# 7880_IO.net
KiCad netlist of a schematic drawn in EAGLE
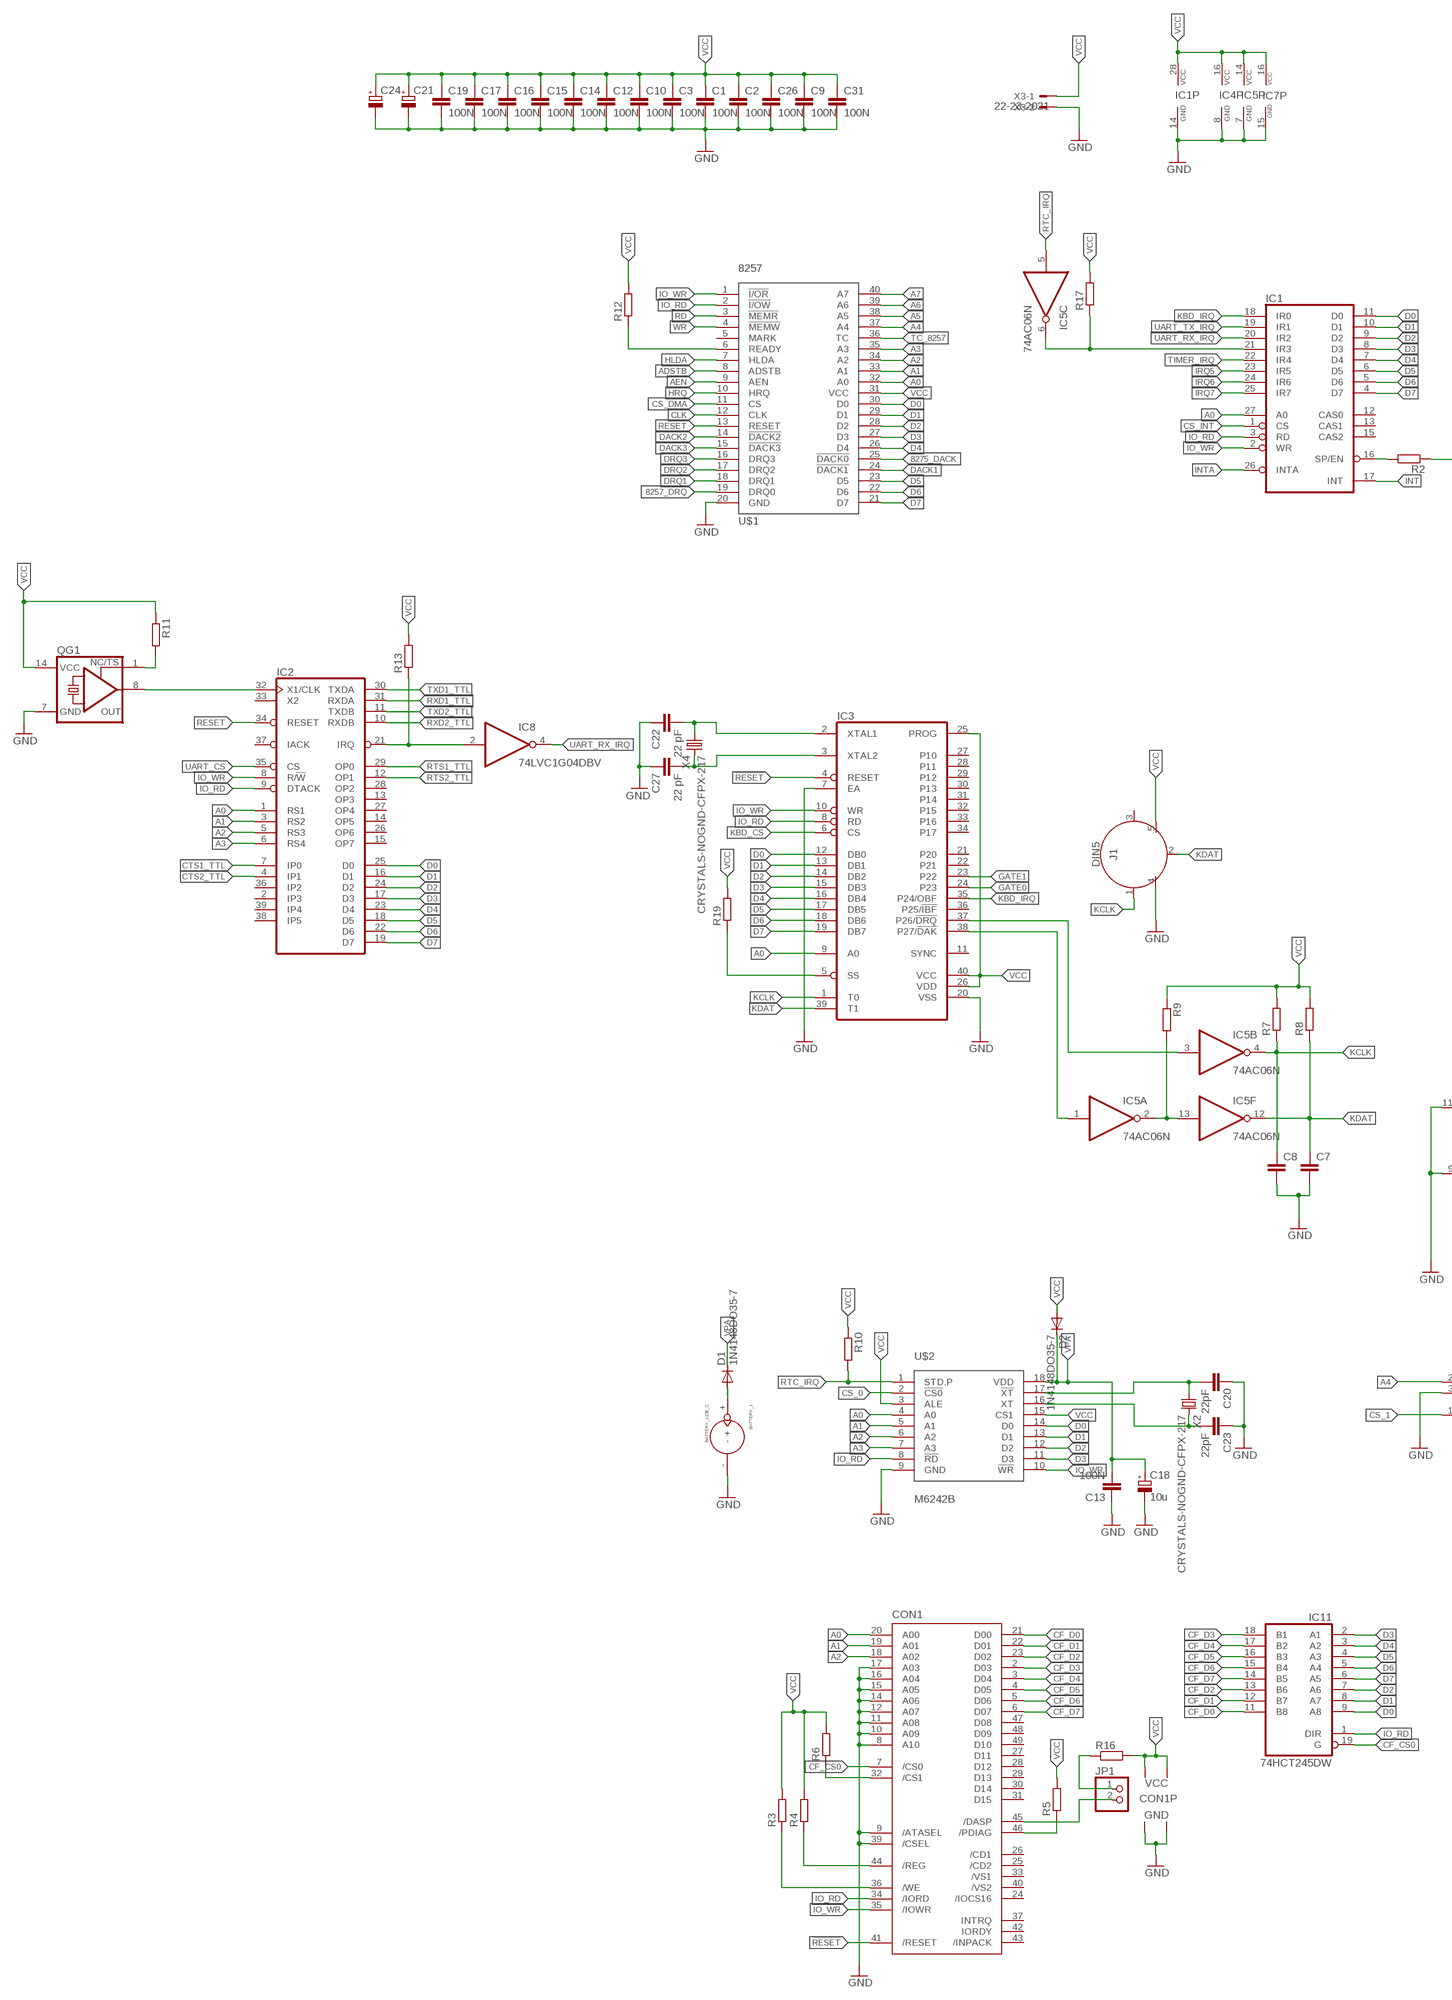
[diagram p0: schematic, sheet 1, part 1 of 2]
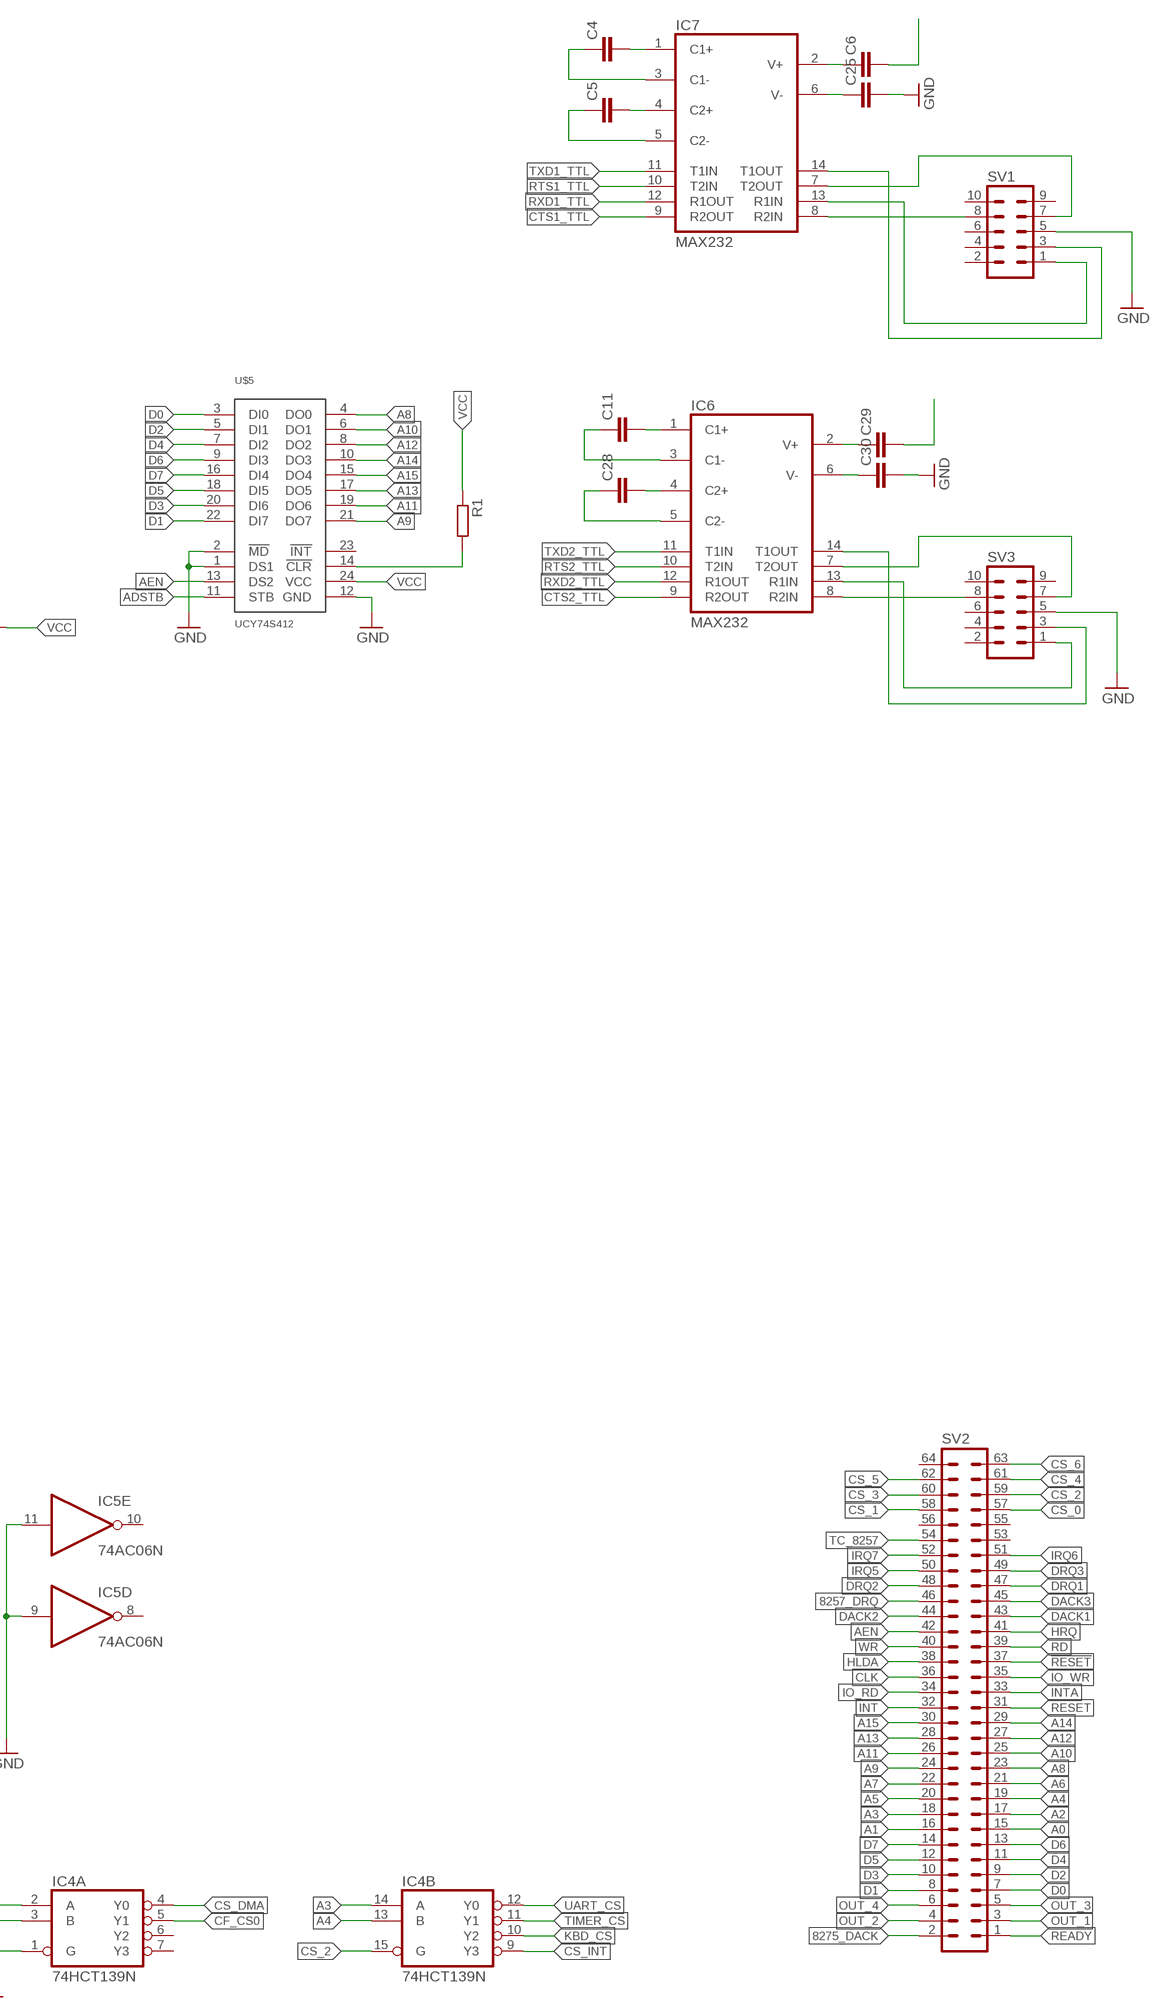
[diagram p1: schematic, sheet 1, part 2 of 2]

(export (version "E")
  (design (tool "Eeschema 10.0.6"))
  (components
    (comp (ref "BATTERY_1")
      (value "BATTERY_1236_C")
      (footprint "eagle-import:BATTERY_1236_C")
      (libsource (lib "eagle-import") (part "BATTERY_1236_C"))
    )
    (comp (ref "C1")
      (value "100N")
      (footprint "eagle-import:C0603")
      (libsource (lib "eagle-import") (part "C-EUC0603"))
    )
    (comp (ref "C2")
      (value "100N")
      (footprint "eagle-import:C0603")
      (libsource (lib "eagle-import") (part "C-EUC0603"))
    )
    (comp (ref "C3")
      (value "100N")
      (footprint "eagle-import:C0603")
      (libsource (lib "eagle-import") (part "C-EUC0603"))
    )
    (comp (ref "C4")
      (value "C-EUC0603")
      (footprint "eagle-import:C0603")
      (libsource (lib "eagle-import") (part "C-EUC0603"))
    )
    (comp (ref "C5")
      (value "C-EUC0603")
      (footprint "eagle-import:C0603")
      (libsource (lib "eagle-import") (part "C-EUC0603"))
    )
    (comp (ref "C6")
      (value "C-EUC0603")
      (footprint "eagle-import:C0603")
      (libsource (lib "eagle-import") (part "C-EUC0603"))
    )
    (comp (ref "C7")
      (value "C-EUC0603")
      (footprint "eagle-import:C0603")
      (libsource (lib "eagle-import") (part "C-EUC0603"))
    )
    (comp (ref "C8")
      (value "C-EUC0603")
      (footprint "eagle-import:C0603")
      (libsource (lib "eagle-import") (part "C-EUC0603"))
    )
    (comp (ref "C9")
      (value "100N")
      (footprint "eagle-import:C0603")
      (libsource (lib "eagle-import") (part "C-EUC0603"))
    )
    (comp (ref "C10")
      (value "100N")
      (footprint "eagle-import:C0603")
      (libsource (lib "eagle-import") (part "C-EUC0603"))
    )
    (comp (ref "C11")
      (value "C-EUC0603")
      (footprint "eagle-import:C0603")
      (libsource (lib "eagle-import") (part "C-EUC0603"))
    )
    (comp (ref "C12")
      (value "100N")
      (footprint "eagle-import:C0603")
      (libsource (lib "eagle-import") (part "C-EUC0603"))
    )
    (comp (ref "C13")
      (value "100N")
      (footprint "eagle-import:C0603")
      (libsource (lib "eagle-import") (part "C-EUC0603"))
    )
    (comp (ref "C14")
      (value "100N")
      (footprint "eagle-import:C0603")
      (libsource (lib "eagle-import") (part "C-EUC0603"))
    )
    (comp (ref "C15")
      (value "100N")
      (footprint "eagle-import:C0603")
      (libsource (lib "eagle-import") (part "C-EUC0603"))
    )
    (comp (ref "C16")
      (value "100N")
      (footprint "eagle-import:C0603")
      (libsource (lib "eagle-import") (part "C-EUC0603"))
    )
    (comp (ref "C17")
      (value "100N")
      (footprint "eagle-import:C0603")
      (libsource (lib "eagle-import") (part "C-EUC0603"))
    )
    (comp (ref "C18")
      (value "10u")
      (footprint "eagle-import:SMC_B")
      (libsource (lib "eagle-import") (part "CPOL-EUSMCB"))
    )
    (comp (ref "C19")
      (value "100N")
      (footprint "eagle-import:C0603")
      (libsource (lib "eagle-import") (part "C-EUC0603"))
    )
    (comp (ref "C20")
      (value "22pF")
      (footprint "eagle-import:C0603")
      (libsource (lib "eagle-import") (part "C-EUC0603"))
    )
    (comp (ref "C21")
      (value "CPOL-EUE3.5-8")
      (footprint "eagle-import:E3,5-8")
      (libsource (lib "eagle-import") (part "CPOL-EUE3.5-8"))
    )
    (comp (ref "C22")
      (value "22 pF")
      (footprint "eagle-import:C0603")
      (libsource (lib "eagle-import") (part "C-EUC0603"))
    )
    (comp (ref "C23")
      (value "22pF")
      (footprint "eagle-import:C0603")
      (libsource (lib "eagle-import") (part "C-EUC0603"))
    )
    (comp (ref "C24")
      (value "CPOL-EUSMCB")
      (footprint "eagle-import:SMC_B")
      (libsource (lib "eagle-import") (part "CPOL-EUSMCB"))
    )
    (comp (ref "C25")
      (value "C-EUC0603")
      (footprint "eagle-import:C0603")
      (libsource (lib "eagle-import") (part "C-EUC0603"))
    )
    (comp (ref "C26")
      (value "100N")
      (footprint "eagle-import:C0603")
      (libsource (lib "eagle-import") (part "C-EUC0603"))
    )
    (comp (ref "C27")
      (value "22 pF")
      (footprint "eagle-import:C0603")
      (libsource (lib "eagle-import") (part "C-EUC0603"))
    )
    (comp (ref "C28")
      (value "C-EUC0603")
      (footprint "eagle-import:C0603")
      (libsource (lib "eagle-import") (part "C-EUC0603"))
    )
    (comp (ref "C29")
      (value "C-EUC0603")
      (footprint "eagle-import:C0603")
      (libsource (lib "eagle-import") (part "C-EUC0603"))
    )
    (comp (ref "C30")
      (value "C-EUC0603")
      (footprint "eagle-import:C0603")
      (libsource (lib "eagle-import") (part "C-EUC0603"))
    )
    (comp (ref "C31")
      (value "100N")
      (footprint "eagle-import:C0603")
      (libsource (lib "eagle-import") (part "C-EUC0603"))
    )
    (comp (ref "CON1")
      (value "CF-CARD-IDE_MODE")
      (footprint "eagle-import:MI20-50PD-SF")
      (libsource (lib "eagle-import") (part "CF-CARD-IDE_MODE"))
    )
    (comp (ref "D1")
      (value "1N4148DO35-7")
      (footprint "eagle-import:DO35-7")
      (libsource (lib "eagle-import") (part "1N4148DO35-7"))
    )
    (comp (ref "D2")
      (value "1N4148DO35-7")
      (footprint "eagle-import:DO35-7")
      (libsource (lib "eagle-import") (part "1N4148DO35-7"))
    )
    (comp (ref "IC1")
      (value "8259A")
      (footprint "eagle-import:DIL28-6")
      (libsource (lib "eagle-import") (part "8259A"))
    )
    (comp (ref "IC2")
      (value "MC68681P")
      (footprint "eagle-import:DIL40")
      (libsource (lib "eagle-import") (part "MC68681P"))
    )
    (comp (ref "IC3")
      (value "UPI-8042AH")
      (footprint "eagle-import:DIL40")
      (libsource (lib "eagle-import") (part "UPI-8042AH"))
    )
    (comp (ref "IC4")
      (value "74HCT139N")
      (footprint "eagle-import:DIL16")
      (libsource (lib "eagle-import") (part "74139NHCT"))
    )
    (comp (ref "IC5")
      (value "74AC06N")
      (footprint "eagle-import:DIL14")
      (libsource (lib "eagle-import") (part "7406NAC"))
    )
    (comp (ref "IC6")
      (value "MAX232")
      (footprint "eagle-import:DIL16")
      (fields (field (name "MF") "MAXIM") (field (name "MPN") "MAX232ACPE+"))
      (libsource (lib "eagle-import") (part "MAX232"))
    )
    (comp (ref "IC7")
      (value "MAX232")
      (footprint "eagle-import:DIL16")
      (fields (field (name "MF") "MAXIM") (field (name "MPN") "MAX232ACPE+"))
      (libsource (lib "eagle-import") (part "MAX232"))
    )
    (comp (ref "IC8")
      (value "74LVC1G04DBV")
      (footprint "eagle-import:SOT23-5")
      (libsource (lib "eagle-import") (part "741G04DBVLVC"))
    )
    (comp (ref "IC11")
      (value "74HCT245DW")
      (footprint "eagle-import:SO20W")
      (libsource (lib "eagle-import") (part "74245DWHCT"))
    )
    (comp (ref "J1")
      (value "DIN5")
      (footprint "eagle-import:DIN5-RA-PTH")
      (libsource (lib "eagle-import") (part "DIN5"))
    )
    (comp (ref "JP1")
      (value "PINHD-1X2")
      (footprint "eagle-import:1X02")
      (libsource (lib "eagle-import") (part "PINHD-1X2"))
    )
    (comp (ref "QG1")
      (value "XO-14")
      (footprint "eagle-import:DIL14S")
      (libsource (lib "eagle-import") (part "XO-14"))
    )
    (comp (ref "R1")
      (value "R-EU_R0603")
      (footprint "eagle-import:R0603")
      (libsource (lib "eagle-import") (part "R-EU_R0603"))
    )
    (comp (ref "R2")
      (value "R-EU_R0603")
      (footprint "eagle-import:R0603")
      (libsource (lib "eagle-import") (part "R-EU_R0603"))
    )
    (comp (ref "R3")
      (value "R-EU_R0603")
      (footprint "eagle-import:R0603")
      (libsource (lib "eagle-import") (part "R-EU_R0603"))
    )
    (comp (ref "R4")
      (value "R-EU_0204/7")
      (footprint "eagle-import:0204_7")
      (libsource (lib "eagle-import") (part "R-EU_0204/7"))
    )
    (comp (ref "R5")
      (value "R-EU_0207/10")
      (footprint "eagle-import:0207_10")
      (libsource (lib "eagle-import") (part "R-EU_0207/10"))
    )
    (comp (ref "R6")
      (value "R-EU_R0603")
      (footprint "eagle-import:R0603")
      (libsource (lib "eagle-import") (part "R-EU_R0603"))
    )
    (comp (ref "R7")
      (value "R-EU_0204/5")
      (footprint "eagle-import:0204_5")
      (libsource (lib "eagle-import") (part "R-EU_0204/5"))
    )
    (comp (ref "R8")
      (value "R-EU_M0805")
      (footprint "eagle-import:M0805")
      (libsource (lib "eagle-import") (part "R-EU_M0805"))
    )
    (comp (ref "R9")
      (value "R-EU_R0603")
      (footprint "eagle-import:R0603")
      (libsource (lib "eagle-import") (part "R-EU_R0603"))
    )
    (comp (ref "R10")
      (value "R-EU_R0603")
      (footprint "eagle-import:R0603")
      (libsource (lib "eagle-import") (part "R-EU_R0603"))
    )
    (comp (ref "R11")
      (value "R-EU_R0603")
      (footprint "eagle-import:R0603")
      (libsource (lib "eagle-import") (part "R-EU_R0603"))
    )
    (comp (ref "R12")
      (value "R-EU_R0603")
      (footprint "eagle-import:R0603")
      (libsource (lib "eagle-import") (part "R-EU_R0603"))
    )
    (comp (ref "R13")
      (value "R-EU_0204/7")
      (footprint "eagle-import:0204_7")
      (libsource (lib "eagle-import") (part "R-EU_0204/7"))
    )
    (comp (ref "R16")
      (value "R-EU_R0603")
      (footprint "eagle-import:R0603")
      (libsource (lib "eagle-import") (part "R-EU_R0603"))
    )
    (comp (ref "R17")
      (value "R-EU_0204/7")
      (footprint "eagle-import:0204_7")
      (libsource (lib "eagle-import") (part "R-EU_0204/7"))
    )
    (comp (ref "R19")
      (value "R-EU_0204/5")
      (footprint "eagle-import:0204_5")
      (libsource (lib "eagle-import") (part "R-EU_0204/5"))
    )
    (comp (ref "SV1")
      (value "ML10")
      (footprint "eagle-import:ML10")
      (libsource (lib "eagle-import") (part "ML10"))
    )
    (comp (ref "SV2")
      (value "ML64L")
      (footprint "eagle-import:ML64L")
      (libsource (lib "eagle-import") (part "ML64L"))
    )
    (comp (ref "SV3")
      (value "ML10")
      (footprint "eagle-import:ML10")
      (libsource (lib "eagle-import") (part "ML10"))
    )
    (comp (ref "U$1")
      (value "8257")
      (footprint "eagle-import:DIL40")
      (libsource (lib "eagle-import") (part "8257"))
    )
    (comp (ref "U$2")
      (value "M6242B")
      (footprint "eagle-import:DIL18")
      (libsource (lib "eagle-import") (part "M6242B"))
    )
    (comp (ref "U$5")
      (value "UCY74S412")
      (footprint "eagle-import:DIL24-6")
      (libsource (lib "eagle-import") (part "UCY74S412"))
    )
    (comp (ref "X2")
      (value "CRYSTALS-NOGND-CFPX-217")
      (footprint "eagle-import:3.2X1.5-2-PAD")
      (libsource (lib "eagle-import") (part "CRYSTALS-NOGND-CFPX-217"))
    )
    (comp (ref "X3")
      (value "22-23-2021")
      (footprint "eagle-import:22-23-2021")
      (fields (field (name "MF") "MOLEX"))
      (libsource (lib "eagle-import") (part "22-23-2021"))
    )
    (comp (ref "X4")
      (value "CRYSTALS-NOGND-CFPX-217")
      (footprint "eagle-import:3.2X1.5-2-PAD")
      (libsource (lib "eagle-import") (part "CRYSTALS-NOGND-CFPX-217"))
    )
  )
  (nets
    (net (code "1") (name "/~{RESET}") (class "Default")
      (node (ref "CON1") (pin "41") (pinfunction "/RESET_41") (pintype "input"))
      (node (ref "IC3") (pin "4") (pinfunction "RESET_4") (pintype "input"))
      (node (ref "SV2") (pin "37") (pinfunction "37_37") (pintype "passive"))
    )
    (net (code "2") (name "8257_DRQ") (class "Default")
      (node (ref "SV2") (pin "46") (pinfunction "46_46") (pintype "passive"))
      (node (ref "U$1") (pin "19") (pinfunction "DRQ0_19") (pintype "bidirectional"))
    )
    (net (code "3") (name "8275_DACK") (class "Default")
      (node (ref "SV2") (pin "2") (pinfunction "2_2") (pintype "passive"))
      (node (ref "U$1") (pin "25") (pinfunction "~{DACK0}_25") (pintype "bidirectional"))
    )
    (net (code "4") (name "A0") (class "Default")
      (node (ref "CON1") (pin "20") (pinfunction "A00_20") (pintype "input"))
      (node (ref "IC1") (pin "27") (pinfunction "A0_27") (pintype "input"))
      (node (ref "IC2") (pin "1") (pinfunction "RS1_1") (pintype "input"))
      (node (ref "IC3") (pin "9") (pinfunction "A0_9") (pintype "input"))
      (node (ref "SV2") (pin "15") (pinfunction "15_15") (pintype "passive"))
      (node (ref "U$1") (pin "32") (pinfunction "A0_32") (pintype "bidirectional"))
      (node (ref "U$2") (pin "4") (pinfunction "A0_4") (pintype "bidirectional"))
    )
    (net (code "5") (name "A1") (class "Default")
      (node (ref "CON1") (pin "19") (pinfunction "A01_19") (pintype "input"))
      (node (ref "IC2") (pin "3") (pinfunction "RS2_3") (pintype "input"))
      (node (ref "SV2") (pin "16") (pinfunction "16_16") (pintype "passive"))
      (node (ref "U$1") (pin "33") (pinfunction "A1_33") (pintype "bidirectional"))
      (node (ref "U$2") (pin "5") (pinfunction "A1_5") (pintype "bidirectional"))
    )
    (net (code "6") (name "A2") (class "Default")
      (node (ref "CON1") (pin "18") (pinfunction "A02_18") (pintype "input"))
      (node (ref "IC2") (pin "5") (pinfunction "RS3_5") (pintype "input"))
      (node (ref "SV2") (pin "17") (pinfunction "17_17") (pintype "passive"))
      (node (ref "U$1") (pin "34") (pinfunction "A2_34") (pintype "bidirectional"))
      (node (ref "U$2") (pin "6") (pinfunction "A2_6") (pintype "bidirectional"))
    )
    (net (code "7") (name "A3") (class "Default")
      (node (ref "IC2") (pin "6") (pinfunction "RS4_6") (pintype "input"))
      (node (ref "IC4") (pin "14") (pinfunction "A_14") (pintype "input"))
      (node (ref "SV2") (pin "18") (pinfunction "18_18") (pintype "passive"))
      (node (ref "U$1") (pin "35") (pinfunction "A3_35") (pintype "bidirectional"))
      (node (ref "U$2") (pin "7") (pinfunction "A3_7") (pintype "bidirectional"))
    )
    (net (code "8") (name "A4") (class "Default")
      (node (ref "IC4") (pin "13") (pinfunction "B_13") (pintype "input"))
      (node (ref "IC4") (pin "2") (pinfunction "A_2") (pintype "input"))
      (node (ref "SV2") (pin "19") (pinfunction "19_19") (pintype "passive"))
      (node (ref "U$1") (pin "37") (pinfunction "A4_37") (pintype "bidirectional"))
    )
    (net (code "9") (name "A5") (class "Default")
      (node (ref "SV2") (pin "20") (pinfunction "20_20") (pintype "passive"))
      (node (ref "U$1") (pin "38") (pinfunction "A5_38") (pintype "bidirectional"))
    )
    (net (code "10") (name "A6") (class "Default")
      (node (ref "SV2") (pin "21") (pinfunction "21_21") (pintype "passive"))
      (node (ref "U$1") (pin "39") (pinfunction "A6_39") (pintype "bidirectional"))
    )
    (net (code "11") (name "A7") (class "Default")
      (node (ref "SV2") (pin "22") (pinfunction "22_22") (pintype "passive"))
      (node (ref "U$1") (pin "40") (pinfunction "A7_40") (pintype "bidirectional"))
    )
    (net (code "12") (name "A8") (class "Default")
      (node (ref "SV2") (pin "23") (pinfunction "23_23") (pintype "passive"))
      (node (ref "U$5") (pin "4") (pinfunction "DO0_4") (pintype "bidirectional"))
    )
    (net (code "13") (name "A9") (class "Default")
      (node (ref "SV2") (pin "24") (pinfunction "24_24") (pintype "passive"))
      (node (ref "U$5") (pin "21") (pinfunction "DO7_21") (pintype "bidirectional"))
    )
    (net (code "14") (name "A10") (class "Default")
      (node (ref "SV2") (pin "25") (pinfunction "25_25") (pintype "passive"))
      (node (ref "U$5") (pin "6") (pinfunction "DO1_6") (pintype "bidirectional"))
    )
    (net (code "15") (name "A11") (class "Default")
      (node (ref "SV2") (pin "26") (pinfunction "26_26") (pintype "passive"))
      (node (ref "U$5") (pin "19") (pinfunction "DO6_19") (pintype "bidirectional"))
    )
    (net (code "16") (name "A12") (class "Default")
      (node (ref "SV2") (pin "27") (pinfunction "27_27") (pintype "passive"))
      (node (ref "U$5") (pin "8") (pinfunction "DO2_8") (pintype "bidirectional"))
    )
    (net (code "17") (name "A13") (class "Default")
      (node (ref "SV2") (pin "28") (pinfunction "28_28") (pintype "passive"))
      (node (ref "U$5") (pin "17") (pinfunction "DO5_17") (pintype "bidirectional"))
    )
    (net (code "18") (name "A14") (class "Default")
      (node (ref "SV2") (pin "29") (pinfunction "29_29") (pintype "passive"))
      (node (ref "U$5") (pin "10") (pinfunction "DO3_10") (pintype "bidirectional"))
    )
    (net (code "19") (name "A15") (class "Default")
      (node (ref "SV2") (pin "30") (pinfunction "30_30") (pintype "passive"))
      (node (ref "U$5") (pin "15") (pinfunction "DO4_15") (pintype "bidirectional"))
    )
    (net (code "20") (name "ADSTB") (class "Default")
      (node (ref "U$1") (pin "8") (pinfunction "ADSTB_8") (pintype "bidirectional"))
      (node (ref "U$5") (pin "11") (pinfunction "STB_11") (pintype "bidirectional"))
    )
    (net (code "21") (name "AEN") (class "Default")
      (node (ref "SV2") (pin "42") (pinfunction "42_42") (pintype "passive"))
      (node (ref "U$1") (pin "9") (pinfunction "AEN_9") (pintype "bidirectional"))
      (node (ref "U$5") (pin "13") (pinfunction "DS2_13") (pintype "bidirectional"))
    )
    (net (code "22") (name "CF_CS0") (class "Default")
      (node (ref "CON1") (pin "7") (pinfunction "/CS0_7") (pintype "input"))
      (node (ref "IC11") (pin "19") (pinfunction "G_19") (pintype "input"))
      (node (ref "IC4") (pin "5") (pinfunction "Y1_5") (pintype "output"))
    )
    (net (code "23") (name "CF_D0") (class "Default")
      (node (ref "CON1") (pin "21") (pinfunction "D00_21") (pintype "bidirectional"))
      (node (ref "IC11") (pin "11") (pinfunction "B8_11") (pintype "bidirectional"))
    )
    (net (code "24") (name "CF_D1") (class "Default")
      (node (ref "CON1") (pin "22") (pinfunction "D01_22") (pintype "bidirectional"))
      (node (ref "IC11") (pin "12") (pinfunction "B7_12") (pintype "bidirectional"))
    )
    (net (code "25") (name "CF_D2") (class "Default")
      (node (ref "CON1") (pin "23") (pinfunction "D02_23") (pintype "bidirectional"))
      (node (ref "IC11") (pin "13") (pinfunction "B6_13") (pintype "bidirectional"))
    )
    (net (code "26") (name "CF_D3") (class "Default")
      (node (ref "CON1") (pin "2") (pinfunction "D03_2") (pintype "bidirectional"))
      (node (ref "IC11") (pin "18") (pinfunction "B1_18") (pintype "bidirectional"))
    )
    (net (code "27") (name "CF_D4") (class "Default")
      (node (ref "CON1") (pin "3") (pinfunction "D04_3") (pintype "bidirectional"))
      (node (ref "IC11") (pin "17") (pinfunction "B2_17") (pintype "bidirectional"))
    )
    (net (code "28") (name "CF_D5") (class "Default")
      (node (ref "CON1") (pin "4") (pinfunction "D05_4") (pintype "bidirectional"))
      (node (ref "IC11") (pin "16") (pinfunction "B3_16") (pintype "bidirectional"))
    )
    (net (code "29") (name "CF_D6") (class "Default")
      (node (ref "CON1") (pin "5") (pinfunction "D06_5") (pintype "bidirectional"))
      (node (ref "IC11") (pin "15") (pinfunction "B4_15") (pintype "bidirectional"))
    )
    (net (code "30") (name "CF_D7") (class "Default")
      (node (ref "CON1") (pin "6") (pinfunction "D07_6") (pintype "bidirectional"))
      (node (ref "IC11") (pin "14") (pinfunction "B5_14") (pintype "bidirectional"))
    )
    (net (code "31") (name "CLK") (class "Default")
      (node (ref "SV2") (pin "36") (pinfunction "36_36") (pintype "passive"))
      (node (ref "U$1") (pin "12") (pinfunction "CLK_12") (pintype "bidirectional"))
    )
    (net (code "32") (name "CS_0") (class "Default")
      (node (ref "SV2") (pin "57") (pinfunction "57_57") (pintype "passive"))
      (node (ref "U$2") (pin "2") (pinfunction "~{CS0}_2") (pintype "bidirectional"))
    )
    (net (code "33") (name "CS_1") (class "Default")
      (node (ref "IC4") (pin "1") (pinfunction "G_1") (pintype "input"))
      (node (ref "SV2") (pin "58") (pinfunction "58_58") (pintype "passive"))
    )
    (net (code "34") (name "CS_2") (class "Default")
      (node (ref "IC4") (pin "15") (pinfunction "G_15") (pintype "input"))
      (node (ref "SV2") (pin "59") (pinfunction "59_59") (pintype "passive"))
    )
    (net (code "35") (name "CS_3") (class "Default")
      (node (ref "SV2") (pin "60") (pinfunction "60_60") (pintype "passive"))
    )
    (net (code "36") (name "CS_4") (class "Default")
      (node (ref "SV2") (pin "61") (pinfunction "61_61") (pintype "passive"))
    )
    (net (code "37") (name "CS_5") (class "Default")
      (node (ref "SV2") (pin "62") (pinfunction "62_62") (pintype "passive"))
    )
    (net (code "38") (name "CS_6") (class "Default")
      (node (ref "SV2") (pin "63") (pinfunction "63_63") (pintype "passive"))
    )
    (net (code "39") (name "CS_DMA") (class "Default")
      (node (ref "IC4") (pin "4") (pinfunction "Y0_4") (pintype "output"))
      (node (ref "U$1") (pin "11") (pinfunction "CS_11") (pintype "bidirectional"))
    )
    (net (code "40") (name "CS_INT") (class "Default")
      (node (ref "IC1") (pin "1") (pinfunction "CS_1") (pintype "input"))
      (node (ref "IC4") (pin "9") (pinfunction "Y3_9") (pintype "output"))
    )
    (net (code "41") (name "CTS1_TTL") (class "Default")
      (node (ref "IC2") (pin "7") (pinfunction "IP0_7") (pintype "input"))
      (node (ref "IC7") (pin "9") (pinfunction "R2OUT_9") (pintype "output"))
    )
    (net (code "42") (name "CTS2_TTL") (class "Default")
      (node (ref "IC2") (pin "4") (pinfunction "IP1_4") (pintype "input"))
      (node (ref "IC6") (pin "9") (pinfunction "R2OUT_9") (pintype "output"))
    )
    (net (code "43") (name "D0") (class "Default")
      (node (ref "IC1") (pin "11") (pinfunction "D0_11") (pintype "bidirectional"))
      (node (ref "IC11") (pin "9") (pinfunction "A8_9") (pintype "bidirectional"))
      (node (ref "IC2") (pin "25") (pinfunction "D0_25") (pintype "bidirectional"))
      (node (ref "IC3") (pin "12") (pinfunction "DB0_12") (pintype "bidirectional"))
      (node (ref "SV2") (pin "7") (pinfunction "7_7") (pintype "passive"))
      (node (ref "U$1") (pin "30") (pinfunction "D0_30") (pintype "bidirectional"))
      (node (ref "U$2") (pin "14") (pinfunction "D0_14") (pintype "bidirectional"))
      (node (ref "U$5") (pin "3") (pinfunction "DI0_3") (pintype "bidirectional"))
    )
    (net (code "44") (name "D1") (class "Default")
      (node (ref "IC1") (pin "10") (pinfunction "D1_10") (pintype "bidirectional"))
      (node (ref "IC11") (pin "8") (pinfunction "A7_8") (pintype "bidirectional"))
      (node (ref "IC2") (pin "16") (pinfunction "D1_16") (pintype "bidirectional"))
      (node (ref "IC3") (pin "13") (pinfunction "DB1_13") (pintype "bidirectional"))
      (node (ref "SV2") (pin "8") (pinfunction "8_8") (pintype "passive"))
      (node (ref "U$1") (pin "29") (pinfunction "D1_29") (pintype "bidirectional"))
      (node (ref "U$2") (pin "13") (pinfunction "D1_13") (pintype "bidirectional"))
      (node (ref "U$5") (pin "22") (pinfunction "DI7_22") (pintype "bidirectional"))
    )
    (net (code "45") (name "D2") (class "Default")
      (node (ref "IC1") (pin "9") (pinfunction "D2_9") (pintype "bidirectional"))
      (node (ref "IC11") (pin "7") (pinfunction "A6_7") (pintype "bidirectional"))
      (node (ref "IC2") (pin "24") (pinfunction "D2_24") (pintype "bidirectional"))
      (node (ref "IC3") (pin "14") (pinfunction "DB2_14") (pintype "bidirectional"))
      (node (ref "SV2") (pin "9") (pinfunction "9_9") (pintype "passive"))
      (node (ref "U$1") (pin "28") (pinfunction "D2_28") (pintype "bidirectional"))
      (node (ref "U$2") (pin "12") (pinfunction "D2_12") (pintype "bidirectional"))
      (node (ref "U$5") (pin "5") (pinfunction "DI1_5") (pintype "bidirectional"))
    )
    (net (code "46") (name "D3") (class "Default")
      (node (ref "IC1") (pin "8") (pinfunction "D3_8") (pintype "bidirectional"))
      (node (ref "IC11") (pin "2") (pinfunction "A1_2") (pintype "bidirectional"))
      (node (ref "IC2") (pin "17") (pinfunction "D3_17") (pintype "bidirectional"))
      (node (ref "IC3") (pin "15") (pinfunction "DB3_15") (pintype "bidirectional"))
      (node (ref "SV2") (pin "10") (pinfunction "10_10") (pintype "passive"))
      (node (ref "U$1") (pin "27") (pinfunction "D3_27") (pintype "bidirectional"))
      (node (ref "U$2") (pin "11") (pinfunction "D3_11") (pintype "bidirectional"))
      (node (ref "U$5") (pin "20") (pinfunction "DI6_20") (pintype "bidirectional"))
    )
    (net (code "47") (name "D4") (class "Default")
      (node (ref "IC1") (pin "7") (pinfunction "D4_7") (pintype "bidirectional"))
      (node (ref "IC11") (pin "3") (pinfunction "A2_3") (pintype "bidirectional"))
      (node (ref "IC2") (pin "23") (pinfunction "D4_23") (pintype "bidirectional"))
      (node (ref "IC3") (pin "16") (pinfunction "DB4_16") (pintype "bidirectional"))
      (node (ref "SV2") (pin "11") (pinfunction "11_11") (pintype "passive"))
      (node (ref "U$1") (pin "26") (pinfunction "D4_26") (pintype "bidirectional"))
      (node (ref "U$5") (pin "7") (pinfunction "DI2_7") (pintype "bidirectional"))
    )
    (net (code "48") (name "D5") (class "Default")
      (node (ref "IC1") (pin "6") (pinfunction "D5_6") (pintype "bidirectional"))
      (node (ref "IC11") (pin "4") (pinfunction "A3_4") (pintype "bidirectional"))
      (node (ref "IC2") (pin "18") (pinfunction "D5_18") (pintype "bidirectional"))
      (node (ref "IC3") (pin "17") (pinfunction "DB5_17") (pintype "bidirectional"))
      (node (ref "SV2") (pin "12") (pinfunction "12_12") (pintype "passive"))
      (node (ref "U$1") (pin "23") (pinfunction "D5_23") (pintype "bidirectional"))
      (node (ref "U$5") (pin "18") (pinfunction "DI5_18") (pintype "bidirectional"))
    )
    (net (code "49") (name "D6") (class "Default")
      (node (ref "IC1") (pin "5") (pinfunction "D6_5") (pintype "bidirectional"))
      (node (ref "IC11") (pin "5") (pinfunction "A4_5") (pintype "bidirectional"))
      (node (ref "IC2") (pin "22") (pinfunction "D6_22") (pintype "bidirectional"))
      (node (ref "IC3") (pin "18") (pinfunction "DB6_18") (pintype "bidirectional"))
      (node (ref "SV2") (pin "13") (pinfunction "13_13") (pintype "passive"))
      (node (ref "U$1") (pin "22") (pinfunction "D6_22") (pintype "bidirectional"))
      (node (ref "U$5") (pin "9") (pinfunction "DI3_9") (pintype "bidirectional"))
    )
    (net (code "50") (name "D7") (class "Default")
      (node (ref "IC1") (pin "4") (pinfunction "D7_4") (pintype "bidirectional"))
      (node (ref "IC11") (pin "6") (pinfunction "A5_6") (pintype "bidirectional"))
      (node (ref "IC2") (pin "19") (pinfunction "D7_19") (pintype "bidirectional"))
      (node (ref "IC3") (pin "19") (pinfunction "DB7_19") (pintype "bidirectional"))
      (node (ref "SV2") (pin "14") (pinfunction "14_14") (pintype "passive"))
      (node (ref "U$1") (pin "21") (pinfunction "D7_21") (pintype "bidirectional"))
      (node (ref "U$5") (pin "16") (pinfunction "DI4_16") (pintype "bidirectional"))
    )
    (net (code "51") (name "DACK1") (class "Default")
      (node (ref "SV2") (pin "43") (pinfunction "43_43") (pintype "passive"))
      (node (ref "U$1") (pin "24") (pinfunction "~{DACK1}_24") (pintype "bidirectional"))
    )
    (net (code "52") (name "DACK2") (class "Default")
      (node (ref "SV2") (pin "44") (pinfunction "44_44") (pintype "passive"))
      (node (ref "U$1") (pin "14") (pinfunction "~{DACK2}_14") (pintype "bidirectional"))
    )
    (net (code "53") (name "DACK3") (class "Default")
      (node (ref "SV2") (pin "45") (pinfunction "45_45") (pintype "passive"))
      (node (ref "U$1") (pin "15") (pinfunction "~{DACK3}_15") (pintype "bidirectional"))
    )
    (net (code "54") (name "DRQ1") (class "Default")
      (node (ref "SV2") (pin "47") (pinfunction "47_47") (pintype "passive"))
      (node (ref "U$1") (pin "18") (pinfunction "DRQ1_18") (pintype "bidirectional"))
    )
    (net (code "55") (name "DRQ2") (class "Default")
      (node (ref "SV2") (pin "48") (pinfunction "48_48") (pintype "passive"))
      (node (ref "U$1") (pin "17") (pinfunction "DRQ2_17") (pintype "bidirectional"))
    )
    (net (code "56") (name "DRQ3") (class "Default")
      (node (ref "SV2") (pin "49") (pinfunction "49_49") (pintype "passive"))
      (node (ref "U$1") (pin "16") (pinfunction "DRQ3_16") (pintype "bidirectional"))
    )
    (net (code "57") (name "GATE0") (class "Default")
      (node (ref "IC3") (pin "24") (pinfunction "P23_24") (pintype "bidirectional"))
    )
    (net (code "58") (name "GATE1") (class "Default")
      (node (ref "IC3") (pin "23") (pinfunction "P22_23") (pintype "bidirectional"))
    )
    (net (code "59") (name "GND") (class "Default")
      (node (ref "BATTERY_1") (pin "-") (pinfunction "-_-") (pintype "bidirectional"))
      (node (ref "C1") (pin "2") (pinfunction "2_2") (pintype "passive"))
      (node (ref "C10") (pin "2") (pinfunction "2_2") (pintype "passive"))
      (node (ref "C12") (pin "2") (pinfunction "2_2") (pintype "passive"))
      (node (ref "C13") (pin "1") (pinfunction "1_1") (pintype "passive"))
      (node (ref "C14") (pin "2") (pinfunction "2_2") (pintype "passive"))
      (node (ref "C15") (pin "2") (pinfunction "2_2") (pintype "passive"))
      (node (ref "C16") (pin "2") (pinfunction "2_2") (pintype "passive"))
      (node (ref "C17") (pin "2") (pinfunction "2_2") (pintype "passive"))
      (node (ref "C18") (pin "-") (pinfunction "-_-") (pintype "passive"))
      (node (ref "C19") (pin "2") (pinfunction "2_2") (pintype "passive"))
      (node (ref "C2") (pin "2") (pinfunction "2_2") (pintype "passive"))
      (node (ref "C20") (pin "1") (pinfunction "1_1") (pintype "passive"))
      (node (ref "C21") (pin "-") (pinfunction "-_-") (pintype "passive"))
      (node (ref "C22") (pin "1") (pinfunction "1_1") (pintype "passive"))
      (node (ref "C23") (pin "1") (pinfunction "1_1") (pintype "passive"))
      (node (ref "C24") (pin "-") (pinfunction "-_-") (pintype "passive"))
      (node (ref "C25") (pin "2") (pinfunction "2_2") (pintype "passive"))
      (node (ref "C26") (pin "2") (pinfunction "2_2") (pintype "passive"))
      (node (ref "C27") (pin "1") (pinfunction "1_1") (pintype "passive"))
      (node (ref "C3") (pin "2") (pinfunction "2_2") (pintype "passive"))
      (node (ref "C30") (pin "2") (pinfunction "2_2") (pintype "passive"))
      (node (ref "C31") (pin "2") (pinfunction "2_2") (pintype "passive"))
      (node (ref "C7") (pin "2") (pinfunction "2_2") (pintype "passive"))
      (node (ref "C8") (pin "2") (pinfunction "2_2") (pintype "passive"))
      (node (ref "C9") (pin "2") (pinfunction "2_2") (pintype "passive"))
      (node (ref "CON1") (pin "1") (pinfunction "GND1_1") (pintype "power_in"))
      (node (ref "CON1") (pin "10") (pinfunction "A09_10") (pintype "input"))
      (node (ref "CON1") (pin "11") (pinfunction "A08_11") (pintype "input"))
      (node (ref "CON1") (pin "12") (pinfunction "A07_12") (pintype "input"))
      (node (ref "CON1") (pin "14") (pinfunction "A06_14") (pintype "input"))
      (node (ref "CON1") (pin "15") (pinfunction "A05_15") (pintype "input"))
      (node (ref "CON1") (pin "16") (pinfunction "A04_16") (pintype "input"))
      (node (ref "CON1") (pin "17") (pinfunction "A03_17") (pintype "input"))
      (node (ref "CON1") (pin "39") (pinfunction "/CSEL_39") (pintype "input"))
      (node (ref "CON1") (pin "50") (pinfunction "GND2_50") (pintype "power_in"))
      (node (ref "CON1") (pin "8") (pinfunction "A10_8") (pintype "input"))
      (node (ref "CON1") (pin "9") (pinfunction "/ATASEL_9") (pintype "input"))
      (node (ref "IC1") (pin "14") (pinfunction "GND_14") (pintype "power_in"))
      (node (ref "IC3") (pin "20") (pinfunction "VSS_20") (pintype "power_in"))
      (node (ref "IC3") (pin "7") (pinfunction "EA_7") (pintype "input"))
      (node (ref "IC4") (pin "3") (pinfunction "B_3") (pintype "input"))
      (node (ref "IC4") (pin "8") (pinfunction "GND_8") (pintype "power_in"))
      (node (ref "IC5") (pin "11") (pinfunction "I_11") (pintype "input"))
      (node (ref "IC5") (pin "7") (pinfunction "GND_7") (pintype "power_in"))
      (node (ref "IC5") (pin "9") (pinfunction "I_9") (pintype "input"))
      (node (ref "IC7") (pin "15") (pinfunction "GND_15") (pintype "power_in"))
      (node (ref "J1") (pin "4") (pinfunction "4_4") (pintype "bidirectional"))
      (node (ref "QG1") (pin "7") (pinfunction "GND_7") (pintype "power_in"))
      (node (ref "SV1") (pin "5") (pinfunction "5_5") (pintype "passive"))
      (node (ref "SV3") (pin "5") (pinfunction "5_5") (pintype "passive"))
      (node (ref "U$1") (pin "20") (pinfunction "GND_20") (pintype "bidirectional"))
      (node (ref "U$2") (pin "9") (pinfunction "GND_9") (pintype "bidirectional"))
      (node (ref "U$5") (pin "1") (pinfunction "DS1_1") (pintype "bidirectional"))
      (node (ref "U$5") (pin "12") (pinfunction "GND_12") (pintype "bidirectional"))
      (node (ref "U$5") (pin "2") (pinfunction "~{MD}_2") (pintype "bidirectional"))
      (node (ref "X3") (pin "2") (pinfunction "S_2") (pintype "passive"))
    )
    (net (code "60") (name "HLDA") (class "Default")
      (node (ref "SV2") (pin "38") (pinfunction "38_38") (pintype "passive"))
      (node (ref "U$1") (pin "7") (pinfunction "HLDA_7") (pintype "bidirectional"))
    )
    (net (code "61") (name "HRQ") (class "Default")
      (node (ref "SV2") (pin "41") (pinfunction "41_41") (pintype "passive"))
      (node (ref "U$1") (pin "10") (pinfunction "HRQ_10") (pintype "bidirectional"))
    )
    (net (code "62") (name "INT") (class "Default")
      (node (ref "IC1") (pin "17") (pinfunction "INT_17") (pintype "output"))
      (node (ref "SV2") (pin "32") (pinfunction "32_32") (pintype "passive"))
    )
    (net (code "63") (name "INTA") (class "Default")
      (node (ref "IC1") (pin "26") (pinfunction "INTA_26") (pintype "input"))
      (node (ref "SV2") (pin "33") (pinfunction "33_33") (pintype "passive"))
    )
    (net (code "64") (name "IO_RD") (class "Default")
      (node (ref "CON1") (pin "34") (pinfunction "/IORD_34") (pintype "input"))
      (node (ref "IC1") (pin "3") (pinfunction "RD_3") (pintype "input"))
      (node (ref "IC11") (pin "1") (pinfunction "DIR_1") (pintype "input"))
      (node (ref "IC2") (pin "9") (pinfunction "DTACK_9") (pintype "output"))
      (node (ref "IC3") (pin "8") (pinfunction "RD_8") (pintype "input"))
      (node (ref "SV2") (pin "34") (pinfunction "34_34") (pintype "passive"))
      (node (ref "U$1") (pin "2") (pinfunction "~{I/OW}_2") (pintype "bidirectional"))
      (node (ref "U$2") (pin "8") (pinfunction "~{RD}_8") (pintype "bidirectional"))
    )
    (net (code "65") (name "IO_WR") (class "Default")
      (node (ref "CON1") (pin "35") (pinfunction "/IOWR_35") (pintype "input"))
      (node (ref "IC1") (pin "2") (pinfunction "WR_2") (pintype "input"))
      (node (ref "IC2") (pin "8") (pinfunction "R/~{W}_8") (pintype "input"))
      (node (ref "IC3") (pin "10") (pinfunction "WR_10") (pintype "input"))
      (node (ref "SV2") (pin "35") (pinfunction "35_35") (pintype "passive"))
      (node (ref "U$1") (pin "1") (pinfunction "~{I/OR}_1") (pintype "bidirectional"))
      (node (ref "U$2") (pin "10") (pinfunction "~{WR}_10") (pintype "bidirectional"))
    )
    (net (code "66") (name "IRQ5") (class "Default")
      (node (ref "IC1") (pin "23") (pinfunction "IR5_23") (pintype "input"))
      (node (ref "SV2") (pin "50") (pinfunction "50_50") (pintype "passive"))
    )
    (net (code "67") (name "IRQ6") (class "Default")
      (node (ref "IC1") (pin "24") (pinfunction "IR6_24") (pintype "input"))
      (node (ref "SV2") (pin "51") (pinfunction "51_51") (pintype "passive"))
    )
    (net (code "68") (name "IRQ7") (class "Default")
      (node (ref "IC1") (pin "25") (pinfunction "IR7_25") (pintype "input"))
      (node (ref "SV2") (pin "52") (pinfunction "52_52") (pintype "passive"))
    )
    (net (code "69") (name "KBD_CS") (class "Default")
      (node (ref "IC3") (pin "6") (pinfunction "CS_6") (pintype "input"))
      (node (ref "IC4") (pin "10") (pinfunction "Y2_10") (pintype "output"))
    )
    (net (code "70") (name "KBD_IRQ") (class "Default")
      (node (ref "IC1") (pin "18") (pinfunction "IR0_18") (pintype "input"))
      (node (ref "IC3") (pin "35") (pinfunction "P24/OBF_35") (pintype "bidirectional"))
    )
    (net (code "71") (name "KCLK") (class "Default")
      (node (ref "C8") (pin "1") (pinfunction "1_1") (pintype "passive"))
      (node (ref "IC3") (pin "1") (pinfunction "T0_1") (pintype "input"))
      (node (ref "IC5") (pin "4") (pinfunction "O_4") (pintype "open_collector"))
      (node (ref "J1") (pin "1") (pinfunction "1_1") (pintype "bidirectional"))
      (node (ref "R7") (pin "1") (pinfunction "1_1") (pintype "passive"))
    )
    (net (code "72") (name "KDAT") (class "Default")
      (node (ref "C7") (pin "1") (pinfunction "1_1") (pintype "passive"))
      (node (ref "IC3") (pin "39") (pinfunction "T1_39") (pintype "input"))
      (node (ref "IC5") (pin "12") (pinfunction "O_12") (pintype "open_collector"))
      (node (ref "J1") (pin "2") (pinfunction "2_2") (pintype "bidirectional"))
      (node (ref "R8") (pin "1") (pinfunction "1_1") (pintype "passive"))
    )
    (net (code "73") (name "Net-(BATTERY_1-Pad+)") (class "Default")
      (node (ref "BATTERY_1") (pin "+") (pinfunction "+_+") (pintype "bidirectional"))
      (node (ref "D1") (pin "A") (pinfunction "A_A") (pintype "passive"))
    )
    (net (code "74") (name "Net-(CON1A-{slash}CS1)") (class "Default")
      (node (ref "CON1") (pin "32") (pinfunction "/CS1_32") (pintype "input"))
      (node (ref "R6") (pin "1") (pinfunction "1_1") (pintype "passive"))
    )
    (net (code "75") (name "Net-(CON1A-{slash}DASP)") (class "Default")
      (node (ref "CON1") (pin "45") (pinfunction "/DASP_45") (pintype "bidirectional"))
      (node (ref "JP1") (pin "2") (pinfunction "2_2") (pintype "passive"))
    )
    (net (code "76") (name "Net-(CON1A-{slash}PDIAG)") (class "Default")
      (node (ref "CON1") (pin "46") (pinfunction "/PDIAG_46") (pintype "bidirectional"))
      (node (ref "R5") (pin "1") (pinfunction "1_1") (pintype "passive"))
    )
    (net (code "77") (name "Net-(CON1A-{slash}REG)") (class "Default")
      (node (ref "CON1") (pin "44") (pinfunction "/REG_44") (pintype "input"))
      (node (ref "R4") (pin "1") (pinfunction "1_1") (pintype "passive"))
    )
    (net (code "78") (name "Net-(CON1A-{slash}WE)") (class "Default")
      (node (ref "CON1") (pin "36") (pinfunction "/WE_36") (pintype "input"))
      (node (ref "R3") (pin "1") (pinfunction "1_1") (pintype "passive"))
    )
    (net (code "79") (name "Net-(IC1A-IR3)") (class "Default")
      (node (ref "IC1") (pin "21") (pinfunction "IR3_21") (pintype "input"))
      (node (ref "IC5") (pin "6") (pinfunction "O_6") (pintype "open_collector"))
      (node (ref "R17") (pin "1") (pinfunction "1_1") (pintype "passive"))
    )
    (net (code "80") (name "Net-(IC1A-SP{slash}EN)") (class "Default")
      (node (ref "IC1") (pin "16") (pinfunction "SP/EN_16") (pintype "bidirectional"))
      (node (ref "R2") (pin "2") (pinfunction "2_2") (pintype "passive"))
    )
    (net (code "81") (name "Net-(IC2A-IRQ)") (class "Default")
      (node (ref "IC2") (pin "21") (pinfunction "IRQ_21") (pintype "output"))
      (node (ref "IC8") (pin "2") (pinfunction "I_2") (pintype "input"))
      (node (ref "R13") (pin "1") (pinfunction "1_1") (pintype "passive"))
    )
    (net (code "82") (name "Net-(IC2A-X1{slash}CLK)") (class "Default")
      (node (ref "IC2") (pin "32") (pinfunction "X1/CLK_32") (pintype "input"))
      (node (ref "QG1") (pin "8") (pinfunction "OUT_8") (pintype "output"))
    )
    (net (code "83") (name "Net-(IC3-P26{slash}~{DRQ})") (class "Default")
      (node (ref "IC3") (pin "37") (pinfunction "P26/~{DRQ}_37") (pintype "bidirectional"))
      (node (ref "IC5") (pin "3") (pinfunction "I_3") (pintype "input"))
    )
    (net (code "84") (name "Net-(IC3-P27{slash}~{DAK})") (class "Default")
      (node (ref "IC3") (pin "38") (pinfunction "P27/~{DAK}_38") (pintype "bidirectional"))
      (node (ref "IC5") (pin "1") (pinfunction "I_1") (pintype "input"))
    )
    (net (code "85") (name "Net-(IC3-SS)") (class "Default")
      (node (ref "IC3") (pin "5") (pinfunction "SS_5") (pintype "input"))
      (node (ref "R19") (pin "1") (pinfunction "1_1") (pintype "passive"))
    )
    (net (code "86") (name "Net-(IC3-XTAL1)") (class "Default")
      (node (ref "C22") (pin "2") (pinfunction "2_2") (pintype "passive"))
      (node (ref "IC3") (pin "2") (pinfunction "XTAL1_2") (pintype "input"))
      (node (ref "X4") (pin "1") (pinfunction "1_1") (pintype "passive"))
    )
    (net (code "87") (name "Net-(IC3-XTAL2)") (class "Default")
      (node (ref "C27") (pin "2") (pinfunction "2_2") (pintype "passive"))
      (node (ref "IC3") (pin "3") (pinfunction "XTAL2_3") (pintype "input"))
      (node (ref "X4") (pin "2") (pinfunction "2_2") (pintype "passive"))
    )
    (net (code "88") (name "Net-(IC5A-O)") (class "Default")
      (node (ref "IC5") (pin "13") (pinfunction "I_13") (pintype "input"))
      (node (ref "IC5") (pin "2") (pinfunction "O_2") (pintype "open_collector"))
      (node (ref "R9") (pin "2") (pinfunction "2_2") (pintype "passive"))
    )
    (net (code "89") (name "Net-(IC6A-C1+)") (class "Default")
      (node (ref "C11") (pin "2") (pinfunction "2_2") (pintype "passive"))
      (node (ref "IC6") (pin "1") (pinfunction "C1+_1") (pintype "bidirectional"))
    )
    (net (code "90") (name "Net-(IC6A-C1-)") (class "Default")
      (node (ref "C11") (pin "1") (pinfunction "1_1") (pintype "passive"))
      (node (ref "IC6") (pin "3") (pinfunction "C1-_3") (pintype "bidirectional"))
    )
    (net (code "91") (name "Net-(IC6A-C2+)") (class "Default")
      (node (ref "C28") (pin "2") (pinfunction "2_2") (pintype "passive"))
      (node (ref "IC6") (pin "4") (pinfunction "C2+_4") (pintype "bidirectional"))
    )
    (net (code "92") (name "Net-(IC6A-C2-)") (class "Default")
      (node (ref "C28") (pin "1") (pinfunction "1_1") (pintype "passive"))
      (node (ref "IC6") (pin "5") (pinfunction "C2-_5") (pintype "bidirectional"))
    )
    (net (code "93") (name "Net-(IC6A-R1IN)") (class "Default")
      (node (ref "IC6") (pin "13") (pinfunction "R1IN_13") (pintype "input"))
      (node (ref "SV3") (pin "1") (pinfunction "1_1") (pintype "passive"))
    )
    (net (code "94") (name "Net-(IC6A-R2IN)") (class "Default")
      (node (ref "IC6") (pin "8") (pinfunction "R2IN_8") (pintype "input"))
      (node (ref "SV3") (pin "8") (pinfunction "8_8") (pintype "passive"))
    )
    (net (code "95") (name "Net-(IC6A-T1OUT)") (class "Default")
      (node (ref "IC6") (pin "14") (pinfunction "T1OUT_14") (pintype "output"))
      (node (ref "SV3") (pin "3") (pinfunction "3_3") (pintype "passive"))
    )
    (net (code "96") (name "Net-(IC6A-T2OUT)") (class "Default")
      (node (ref "IC6") (pin "7") (pinfunction "T2OUT_7") (pintype "output"))
      (node (ref "SV3") (pin "7") (pinfunction "7_7") (pintype "passive"))
    )
    (net (code "97") (name "Net-(IC6A-V+)") (class "Default")
      (node (ref "C29") (pin "1") (pinfunction "1_1") (pintype "passive"))
      (node (ref "IC6") (pin "2") (pinfunction "V+_2") (pintype "bidirectional"))
    )
    (net (code "98") (name "Net-(IC6A-V-)") (class "Default")
      (node (ref "C30") (pin "1") (pinfunction "1_1") (pintype "passive"))
      (node (ref "IC6") (pin "6") (pinfunction "V-_6") (pintype "bidirectional"))
    )
    (net (code "99") (name "Net-(IC7A-C1+)") (class "Default")
      (node (ref "C4") (pin "2") (pinfunction "2_2") (pintype "passive"))
      (node (ref "IC7") (pin "1") (pinfunction "C1+_1") (pintype "bidirectional"))
    )
    (net (code "100") (name "Net-(IC7A-C1-)") (class "Default")
      (node (ref "C4") (pin "1") (pinfunction "1_1") (pintype "passive"))
      (node (ref "IC7") (pin "3") (pinfunction "C1-_3") (pintype "bidirectional"))
    )
    (net (code "101") (name "Net-(IC7A-C2+)") (class "Default")
      (node (ref "C5") (pin "2") (pinfunction "2_2") (pintype "passive"))
      (node (ref "IC7") (pin "4") (pinfunction "C2+_4") (pintype "bidirectional"))
    )
    (net (code "102") (name "Net-(IC7A-C2-)") (class "Default")
      (node (ref "C5") (pin "1") (pinfunction "1_1") (pintype "passive"))
      (node (ref "IC7") (pin "5") (pinfunction "C2-_5") (pintype "bidirectional"))
    )
    (net (code "103") (name "Net-(IC7A-R1IN)") (class "Default")
      (node (ref "IC7") (pin "13") (pinfunction "R1IN_13") (pintype "input"))
      (node (ref "SV1") (pin "1") (pinfunction "1_1") (pintype "passive"))
    )
    (net (code "104") (name "Net-(IC7A-R2IN)") (class "Default")
      (node (ref "IC7") (pin "8") (pinfunction "R2IN_8") (pintype "input"))
      (node (ref "SV1") (pin "8") (pinfunction "8_8") (pintype "passive"))
    )
    (net (code "105") (name "Net-(IC7A-T1OUT)") (class "Default")
      (node (ref "IC7") (pin "14") (pinfunction "T1OUT_14") (pintype "output"))
      (node (ref "SV1") (pin "3") (pinfunction "3_3") (pintype "passive"))
    )
    (net (code "106") (name "Net-(IC7A-T2OUT)") (class "Default")
      (node (ref "IC7") (pin "7") (pinfunction "T2OUT_7") (pintype "output"))
      (node (ref "SV1") (pin "7") (pinfunction "7_7") (pintype "passive"))
    )
    (net (code "107") (name "Net-(IC7A-V+)") (class "Default")
      (node (ref "C6") (pin "1") (pinfunction "1_1") (pintype "passive"))
      (node (ref "IC7") (pin "2") (pinfunction "V+_2") (pintype "bidirectional"))
    )
    (net (code "108") (name "Net-(IC7A-V-)") (class "Default")
      (node (ref "C25") (pin "1") (pinfunction "1_1") (pintype "passive"))
      (node (ref "IC7") (pin "6") (pinfunction "V-_6") (pintype "bidirectional"))
    )
    (net (code "109") (name "Net-(JP1-Pad1)") (class "Default")
      (node (ref "JP1") (pin "1") (pinfunction "1_1") (pintype "passive"))
      (node (ref "R16") (pin "1") (pinfunction "1_1") (pintype "passive"))
    )
    (net (code "110") (name "Net-(QG1-TS)") (class "Default")
      (node (ref "QG1") (pin "1") (pinfunction "TS_1") (pintype "passive"))
      (node (ref "R11") (pin "2") (pinfunction "2_2") (pintype "passive"))
    )
    (net (code "111") (name "Net-(U$1-READY)") (class "Default")
      (node (ref "R12") (pin "1") (pinfunction "1_1") (pintype "passive"))
      (node (ref "U$1") (pin "6") (pinfunction "READY_6") (pintype "bidirectional"))
    )
    (net (code "112") (name "Net-(U$2-XT)") (class "Default")
      (node (ref "C23") (pin "2") (pinfunction "2_2") (pintype "passive"))
      (node (ref "U$2") (pin "16") (pinfunction "XT_16") (pintype "bidirectional"))
      (node (ref "X2") (pin "2") (pinfunction "2_2") (pintype "passive"))
    )
    (net (code "113") (name "Net-(U$2-~{XT})") (class "Default")
      (node (ref "C20") (pin "2") (pinfunction "2_2") (pintype "passive"))
      (node (ref "U$2") (pin "17") (pinfunction "~{XT}_17") (pintype "bidirectional"))
      (node (ref "X2") (pin "1") (pinfunction "1_1") (pintype "passive"))
    )
    (net (code "114") (name "Net-(U$5-~{CLR})") (class "Default")
      (node (ref "R1") (pin "2") (pinfunction "2_2") (pintype "passive"))
      (node (ref "U$5") (pin "14") (pinfunction "~{CLR}_14") (pintype "bidirectional"))
    )
    (net (code "115") (name "OUT_1") (class "Default")
      (node (ref "SV2") (pin "3") (pinfunction "3_3") (pintype "passive"))
    )
    (net (code "116") (name "OUT_2") (class "Default")
      (node (ref "SV2") (pin "4") (pinfunction "4_4") (pintype "passive"))
    )
    (net (code "117") (name "OUT_3") (class "Default")
      (node (ref "SV2") (pin "5") (pinfunction "5_5") (pintype "passive"))
    )
    (net (code "118") (name "OUT_4") (class "Default")
      (node (ref "SV2") (pin "6") (pinfunction "6_6") (pintype "passive"))
    )
    (net (code "119") (name "RD") (class "Default")
      (node (ref "SV2") (pin "39") (pinfunction "39_39") (pintype "passive"))
      (node (ref "U$1") (pin "3") (pinfunction "~{MEMR}_3") (pintype "bidirectional"))
    )
    (net (code "120") (name "READY") (class "Default")
      (node (ref "SV2") (pin "1") (pinfunction "1_1") (pintype "passive"))
    )
    (net (code "121") (name "RESET") (class "Default")
      (node (ref "IC2") (pin "34") (pinfunction "RESET_34") (pintype "input"))
      (node (ref "SV2") (pin "31") (pinfunction "31_31") (pintype "passive"))
      (node (ref "U$1") (pin "13") (pinfunction "RESET_13") (pintype "bidirectional"))
    )
    (net (code "122") (name "RTC_IRQ") (class "Default")
      (node (ref "IC5") (pin "5") (pinfunction "I_5") (pintype "input"))
      (node (ref "R10") (pin "2") (pinfunction "2_2") (pintype "passive"))
      (node (ref "U$2") (pin "1") (pinfunction "STD.P_1") (pintype "bidirectional"))
    )
    (net (code "123") (name "RTS1_TTL") (class "Default")
      (node (ref "IC2") (pin "29") (pinfunction "OP0_29") (pintype "output"))
      (node (ref "IC7") (pin "10") (pinfunction "T2IN_10") (pintype "input"))
    )
    (net (code "124") (name "RTS2_TTL") (class "Default")
      (node (ref "IC2") (pin "12") (pinfunction "OP1_12") (pintype "output"))
      (node (ref "IC6") (pin "10") (pinfunction "T2IN_10") (pintype "input"))
    )
    (net (code "125") (name "RXD1_TTL") (class "Default")
      (node (ref "IC2") (pin "31") (pinfunction "RXDA_31") (pintype "input"))
      (node (ref "IC7") (pin "12") (pinfunction "R1OUT_12") (pintype "output"))
    )
    (net (code "126") (name "RXD2_TTL") (class "Default")
      (node (ref "IC2") (pin "10") (pinfunction "RXDB_10") (pintype "output"))
      (node (ref "IC6") (pin "12") (pinfunction "R1OUT_12") (pintype "output"))
    )
    (net (code "127") (name "TC_8257") (class "Default")
      (node (ref "SV2") (pin "54") (pinfunction "54_54") (pintype "passive"))
      (node (ref "U$1") (pin "36") (pinfunction "TC_36") (pintype "bidirectional"))
    )
    (net (code "128") (name "TIMER_CS") (class "Default")
      (node (ref "IC4") (pin "11") (pinfunction "Y1_11") (pintype "output"))
    )
    (net (code "129") (name "TIMER_IRQ") (class "Default")
      (node (ref "IC1") (pin "22") (pinfunction "IR4_22") (pintype "input"))
    )
    (net (code "130") (name "TXD1_TTL") (class "Default")
      (node (ref "IC2") (pin "30") (pinfunction "TXDA_30") (pintype "output"))
      (node (ref "IC7") (pin "11") (pinfunction "T1IN_11") (pintype "input"))
    )
    (net (code "131") (name "TXD2_TTL") (class "Default")
      (node (ref "IC2") (pin "11") (pinfunction "TXDB_11") (pintype "bidirectional"))
      (node (ref "IC6") (pin "11") (pinfunction "T1IN_11") (pintype "input"))
    )
    (net (code "132") (name "UART_CS") (class "Default")
      (node (ref "IC2") (pin "35") (pinfunction "CS_35") (pintype "input"))
      (node (ref "IC4") (pin "12") (pinfunction "Y0_12") (pintype "output"))
    )
    (net (code "133") (name "UART_RX_IRQ") (class "Default")
      (node (ref "IC1") (pin "20") (pinfunction "IR2_20") (pintype "input"))
      (node (ref "IC8") (pin "4") (pinfunction "O_4") (pintype "output"))
    )
    (net (code "134") (name "UART_TX_IRQ") (class "Default")
      (node (ref "IC1") (pin "19") (pinfunction "IR1_19") (pintype "input"))
    )
    (net (code "135") (name "VCC") (class "Default")
      (node (ref "C1") (pin "1") (pinfunction "1_1") (pintype "passive"))
      (node (ref "C10") (pin "1") (pinfunction "1_1") (pintype "passive"))
      (node (ref "C12") (pin "1") (pinfunction "1_1") (pintype "passive"))
      (node (ref "C14") (pin "1") (pinfunction "1_1") (pintype "passive"))
      (node (ref "C15") (pin "1") (pinfunction "1_1") (pintype "passive"))
      (node (ref "C16") (pin "1") (pinfunction "1_1") (pintype "passive"))
      (node (ref "C17") (pin "1") (pinfunction "1_1") (pintype "passive"))
      (node (ref "C19") (pin "1") (pinfunction "1_1") (pintype "passive"))
      (node (ref "C2") (pin "1") (pinfunction "1_1") (pintype "passive"))
      (node (ref "C21") (pin "+") (pinfunction "+_+") (pintype "passive"))
      (node (ref "C24") (pin "+") (pinfunction "+_+") (pintype "passive"))
      (node (ref "C26") (pin "1") (pinfunction "1_1") (pintype "passive"))
      (node (ref "C29") (pin "2") (pinfunction "2_2") (pintype "passive"))
      (node (ref "C3") (pin "1") (pinfunction "1_1") (pintype "passive"))
      (node (ref "C31") (pin "1") (pinfunction "1_1") (pintype "passive"))
      (node (ref "C6") (pin "2") (pinfunction "2_2") (pintype "passive"))
      (node (ref "C9") (pin "1") (pinfunction "1_1") (pintype "passive"))
      (node (ref "CON1") (pin "13") (pinfunction "VCC2_13") (pintype "power_in"))
      (node (ref "CON1") (pin "38") (pinfunction "VCC1_38") (pintype "power_in"))
      (node (ref "D2") (pin "A") (pinfunction "A_A") (pintype "passive"))
      (node (ref "IC1") (pin "28") (pinfunction "VCC_28") (pintype "power_in"))
      (node (ref "IC3") (pin "25") (pinfunction "PROG_25") (pintype "bidirectional"))
      (node (ref "IC3") (pin "26") (pinfunction "VDD_26") (pintype "power_in"))
      (node (ref "IC3") (pin "40") (pinfunction "VCC_40") (pintype "power_in"))
      (node (ref "IC4") (pin "16") (pinfunction "VCC_16") (pintype "power_in"))
      (node (ref "IC5") (pin "14") (pinfunction "VCC_14") (pintype "power_in"))
      (node (ref "IC7") (pin "16") (pinfunction "VCC_16") (pintype "power_in"))
      (node (ref "J1") (pin "5") (pinfunction "5_5") (pintype "bidirectional"))
      (node (ref "QG1") (pin "14") (pinfunction "VCC_14") (pintype "power_in"))
      (node (ref "R1") (pin "1") (pinfunction "1_1") (pintype "passive"))
      (node (ref "R10") (pin "1") (pinfunction "1_1") (pintype "passive"))
      (node (ref "R11") (pin "1") (pinfunction "1_1") (pintype "passive"))
      (node (ref "R12") (pin "2") (pinfunction "2_2") (pintype "passive"))
      (node (ref "R13") (pin "2") (pinfunction "2_2") (pintype "passive"))
      (node (ref "R16") (pin "2") (pinfunction "2_2") (pintype "passive"))
      (node (ref "R17") (pin "2") (pinfunction "2_2") (pintype "passive"))
      (node (ref "R19") (pin "2") (pinfunction "2_2") (pintype "passive"))
      (node (ref "R2") (pin "1") (pinfunction "1_1") (pintype "passive"))
      (node (ref "R3") (pin "2") (pinfunction "2_2") (pintype "passive"))
      (node (ref "R4") (pin "2") (pinfunction "2_2") (pintype "passive"))
      (node (ref "R5") (pin "2") (pinfunction "2_2") (pintype "passive"))
      (node (ref "R6") (pin "2") (pinfunction "2_2") (pintype "passive"))
      (node (ref "R7") (pin "2") (pinfunction "2_2") (pintype "passive"))
      (node (ref "R8") (pin "2") (pinfunction "2_2") (pintype "passive"))
      (node (ref "R9") (pin "1") (pinfunction "1_1") (pintype "passive"))
      (node (ref "U$1") (pin "31") (pinfunction "VCC_31") (pintype "bidirectional"))
      (node (ref "U$2") (pin "15") (pinfunction "CS1_15") (pintype "bidirectional"))
      (node (ref "U$2") (pin "3") (pinfunction "ALE_3") (pintype "bidirectional"))
      (node (ref "U$5") (pin "24") (pinfunction "VCC_24") (pintype "bidirectional"))
      (node (ref "X3") (pin "1") (pinfunction "S_1") (pintype "passive"))
    )
    (net (code "136") (name "VPA") (class "Default")
      (node (ref "C13") (pin "2") (pinfunction "2_2") (pintype "passive"))
      (node (ref "C18") (pin "+") (pinfunction "+_+") (pintype "passive"))
      (node (ref "D1") (pin "C") (pinfunction "C_C") (pintype "passive"))
      (node (ref "D2") (pin "C") (pinfunction "C_C") (pintype "passive"))
      (node (ref "U$2") (pin "18") (pinfunction "VDD_18") (pintype "bidirectional"))
    )
    (net (code "137") (name "WR") (class "Default")
      (node (ref "SV2") (pin "40") (pinfunction "40_40") (pintype "passive"))
      (node (ref "U$1") (pin "4") (pinfunction "~{MEMW}_4") (pintype "bidirectional"))
    )
    (net (code "138") (name "unconnected-(CON1A-D08-Pad47)") (class "Default")
      (node (ref "CON1") (pin "47") (pinfunction "D08_47") (pintype "bidirectional"))
    )
    (net (code "139") (name "unconnected-(CON1A-D09-Pad48)") (class "Default")
      (node (ref "CON1") (pin "48") (pinfunction "D09_48") (pintype "bidirectional"))
    )
    (net (code "140") (name "unconnected-(CON1A-D10-Pad49)") (class "Default")
      (node (ref "CON1") (pin "49") (pinfunction "D10_49") (pintype "bidirectional"))
    )
    (net (code "141") (name "unconnected-(CON1A-D11-Pad27)") (class "Default")
      (node (ref "CON1") (pin "27") (pinfunction "D11_27") (pintype "bidirectional"))
    )
    (net (code "142") (name "unconnected-(CON1A-D12-Pad28)") (class "Default")
      (node (ref "CON1") (pin "28") (pinfunction "D12_28") (pintype "bidirectional"))
    )
    (net (code "143") (name "unconnected-(CON1A-D13-Pad29)") (class "Default")
      (node (ref "CON1") (pin "29") (pinfunction "D13_29") (pintype "bidirectional"))
    )
    (net (code "144") (name "unconnected-(CON1A-D14-Pad30)") (class "Default")
      (node (ref "CON1") (pin "30") (pinfunction "D14_30") (pintype "bidirectional"))
    )
    (net (code "145") (name "unconnected-(CON1A-D15-Pad31)") (class "Default")
      (node (ref "CON1") (pin "31") (pinfunction "D15_31") (pintype "bidirectional"))
    )
    (net (code "146") (name "unconnected-(CON1A-INTRQ-Pad37)") (class "Default")
      (node (ref "CON1") (pin "37") (pinfunction "INTRQ_37") (pintype "output"))
    )
    (net (code "147") (name "unconnected-(CON1A-IORDY-Pad42)") (class "Default")
      (node (ref "CON1") (pin "42") (pinfunction "IORDY_42") (pintype "output"))
    )
    (net (code "148") (name "unconnected-(CON1A-{slash}CD1-Pad26)") (class "Default")
      (node (ref "CON1") (pin "26") (pinfunction "/CD1_26") (pintype "output"))
    )
    (net (code "149") (name "unconnected-(CON1A-{slash}CD2-Pad25)") (class "Default")
      (node (ref "CON1") (pin "25") (pinfunction "/CD2_25") (pintype "output"))
    )
    (net (code "150") (name "unconnected-(CON1A-{slash}INPACK-Pad43)") (class "Default")
      (node (ref "CON1") (pin "43") (pinfunction "/INPACK_43") (pintype "output"))
    )
    (net (code "151") (name "unconnected-(CON1A-{slash}IOCS16-Pad24)") (class "Default")
      (node (ref "CON1") (pin "24") (pinfunction "/IOCS16_24") (pintype "output"))
    )
    (net (code "152") (name "unconnected-(CON1A-{slash}VS1-Pad33)") (class "Default")
      (node (ref "CON1") (pin "33") (pinfunction "/VS1_33") (pintype "output"))
    )
    (net (code "153") (name "unconnected-(CON1A-{slash}VS2-Pad40)") (class "Default")
      (node (ref "CON1") (pin "40") (pinfunction "/VS2_40") (pintype "output"))
    )
    (net (code "154") (name "unconnected-(IC1A-CAS0-Pad12)") (class "Default")
      (node (ref "IC1") (pin "12") (pinfunction "CAS0_12") (pintype "bidirectional"))
    )
    (net (code "155") (name "unconnected-(IC1A-CAS1-Pad13)") (class "Default")
      (node (ref "IC1") (pin "13") (pinfunction "CAS1_13") (pintype "bidirectional"))
    )
    (net (code "156") (name "unconnected-(IC1A-CAS2-Pad15)") (class "Default")
      (node (ref "IC1") (pin "15") (pinfunction "CAS2_15") (pintype "bidirectional"))
    )
    (net (code "157") (name "unconnected-(IC2A-IACK-Pad37)") (class "Default")
      (node (ref "IC2") (pin "37") (pinfunction "IACK_37") (pintype "input"))
    )
    (net (code "158") (name "unconnected-(IC2A-IP2-Pad36)") (class "Default")
      (node (ref "IC2") (pin "36") (pinfunction "IP2_36") (pintype "input"))
    )
    (net (code "159") (name "unconnected-(IC2A-IP3-Pad2)") (class "Default")
      (node (ref "IC2") (pin "2") (pinfunction "IP3_2") (pintype "input"))
    )
    (net (code "160") (name "unconnected-(IC2A-IP4-Pad39)") (class "Default")
      (node (ref "IC2") (pin "39") (pinfunction "IP4_39") (pintype "input"))
    )
    (net (code "161") (name "unconnected-(IC2A-IP5-Pad38)") (class "Default")
      (node (ref "IC2") (pin "38") (pinfunction "IP5_38") (pintype "input"))
    )
    (net (code "162") (name "unconnected-(IC2A-OP2-Pad28)") (class "Default")
      (node (ref "IC2") (pin "28") (pinfunction "OP2_28") (pintype "output"))
    )
    (net (code "163") (name "unconnected-(IC2A-OP3-Pad13)") (class "Default")
      (node (ref "IC2") (pin "13") (pinfunction "OP3_13") (pintype "output"))
    )
    (net (code "164") (name "unconnected-(IC2A-OP4-Pad27)") (class "Default")
      (node (ref "IC2") (pin "27") (pinfunction "OP4_27") (pintype "output"))
    )
    (net (code "165") (name "unconnected-(IC2A-OP5-Pad14)") (class "Default")
      (node (ref "IC2") (pin "14") (pinfunction "OP5_14") (pintype "output"))
    )
    (net (code "166") (name "unconnected-(IC2A-OP6-Pad26)") (class "Default")
      (node (ref "IC2") (pin "26") (pinfunction "OP6_26") (pintype "output"))
    )
    (net (code "167") (name "unconnected-(IC2A-OP7-Pad15)") (class "Default")
      (node (ref "IC2") (pin "15") (pinfunction "OP7_15") (pintype "output"))
    )
    (net (code "168") (name "unconnected-(IC2A-X2-Pad33)") (class "Default")
      (node (ref "IC2") (pin "33") (pinfunction "X2_33") (pintype "output"))
    )
    (net (code "169") (name "unconnected-(IC3-P10-Pad27)") (class "Default")
      (node (ref "IC3") (pin "27") (pinfunction "P10_27") (pintype "bidirectional"))
    )
    (net (code "170") (name "unconnected-(IC3-P11-Pad28)") (class "Default")
      (node (ref "IC3") (pin "28") (pinfunction "P11_28") (pintype "bidirectional"))
    )
    (net (code "171") (name "unconnected-(IC3-P12-Pad29)") (class "Default")
      (node (ref "IC3") (pin "29") (pinfunction "P12_29") (pintype "bidirectional"))
    )
    (net (code "172") (name "unconnected-(IC3-P13-Pad30)") (class "Default")
      (node (ref "IC3") (pin "30") (pinfunction "P13_30") (pintype "bidirectional"))
    )
    (net (code "173") (name "unconnected-(IC3-P14-Pad31)") (class "Default")
      (node (ref "IC3") (pin "31") (pinfunction "P14_31") (pintype "bidirectional"))
    )
    (net (code "174") (name "unconnected-(IC3-P15-Pad32)") (class "Default")
      (node (ref "IC3") (pin "32") (pinfunction "P15_32") (pintype "bidirectional"))
    )
    (net (code "175") (name "unconnected-(IC3-P16-Pad33)") (class "Default")
      (node (ref "IC3") (pin "33") (pinfunction "P16_33") (pintype "bidirectional"))
    )
    (net (code "176") (name "unconnected-(IC3-P17-Pad34)") (class "Default")
      (node (ref "IC3") (pin "34") (pinfunction "P17_34") (pintype "bidirectional"))
    )
    (net (code "177") (name "unconnected-(IC3-P20-Pad21)") (class "Default")
      (node (ref "IC3") (pin "21") (pinfunction "P20_21") (pintype "bidirectional"))
    )
    (net (code "178") (name "unconnected-(IC3-P21-Pad22)") (class "Default")
      (node (ref "IC3") (pin "22") (pinfunction "P21_22") (pintype "bidirectional"))
    )
    (net (code "179") (name "unconnected-(IC3-P25{slash}~{IBF}-Pad36)") (class "Default")
      (node (ref "IC3") (pin "36") (pinfunction "P25/~{IBF}_36") (pintype "bidirectional"))
    )
    (net (code "180") (name "unconnected-(IC3-SYNC-Pad11)") (class "Default")
      (node (ref "IC3") (pin "11") (pinfunction "SYNC_11") (pintype "output"))
    )
    (net (code "181") (name "unconnected-(IC4A-Y2-Pad6)") (class "Default")
      (node (ref "IC4") (pin "6") (pinfunction "Y2_6") (pintype "output"))
    )
    (net (code "182") (name "unconnected-(IC4A-Y3-Pad7)") (class "Default")
      (node (ref "IC4") (pin "7") (pinfunction "Y3_7") (pintype "output"))
    )
    (net (code "183") (name "unconnected-(IC5D-O-Pad8)") (class "Default")
      (node (ref "IC5") (pin "8") (pinfunction "O_8") (pintype "open_collector"))
    )
    (net (code "184") (name "unconnected-(IC5E-O-Pad10)") (class "Default")
      (node (ref "IC5") (pin "10") (pinfunction "O_10") (pintype "open_collector"))
    )
    (net (code "185") (name "unconnected-(J1-Pad3)") (class "Default")
      (node (ref "J1") (pin "3") (pinfunction "3_3") (pintype "bidirectional"))
    )
    (net (code "186") (name "unconnected-(SV1-Pad2)") (class "Default")
      (node (ref "SV1") (pin "2") (pinfunction "2_2") (pintype "passive"))
    )
    (net (code "187") (name "unconnected-(SV1-Pad4)") (class "Default")
      (node (ref "SV1") (pin "4") (pinfunction "4_4") (pintype "passive"))
    )
    (net (code "188") (name "unconnected-(SV1-Pad6)") (class "Default")
      (node (ref "SV1") (pin "6") (pinfunction "6_6") (pintype "passive"))
    )
    (net (code "189") (name "unconnected-(SV1-Pad9)") (class "Default")
      (node (ref "SV1") (pin "9") (pinfunction "9_9") (pintype "passive"))
    )
    (net (code "190") (name "unconnected-(SV1-Pad10)") (class "Default")
      (node (ref "SV1") (pin "10") (pinfunction "10_10") (pintype "passive"))
    )
    (net (code "191") (name "unconnected-(SV2-Pad53)") (class "Default")
      (node (ref "SV2") (pin "53") (pinfunction "53_53") (pintype "passive"))
    )
    (net (code "192") (name "unconnected-(SV2-Pad55)") (class "Default")
      (node (ref "SV2") (pin "55") (pinfunction "55_55") (pintype "passive"))
    )
    (net (code "193") (name "unconnected-(SV2-Pad56)") (class "Default")
      (node (ref "SV2") (pin "56") (pinfunction "56_56") (pintype "passive"))
    )
    (net (code "194") (name "unconnected-(SV2-Pad64)") (class "Default")
      (node (ref "SV2") (pin "64") (pinfunction "64_64") (pintype "passive"))
    )
    (net (code "195") (name "unconnected-(SV3-Pad2)") (class "Default")
      (node (ref "SV3") (pin "2") (pinfunction "2_2") (pintype "passive"))
    )
    (net (code "196") (name "unconnected-(SV3-Pad4)") (class "Default")
      (node (ref "SV3") (pin "4") (pinfunction "4_4") (pintype "passive"))
    )
    (net (code "197") (name "unconnected-(SV3-Pad6)") (class "Default")
      (node (ref "SV3") (pin "6") (pinfunction "6_6") (pintype "passive"))
    )
    (net (code "198") (name "unconnected-(SV3-Pad9)") (class "Default")
      (node (ref "SV3") (pin "9") (pinfunction "9_9") (pintype "passive"))
    )
    (net (code "199") (name "unconnected-(SV3-Pad10)") (class "Default")
      (node (ref "SV3") (pin "10") (pinfunction "10_10") (pintype "passive"))
    )
    (net (code "200") (name "unconnected-(U$1-MARK-Pad5)") (class "Default")
      (node (ref "U$1") (pin "5") (pinfunction "MARK_5") (pintype "bidirectional"))
    )
    (net (code "201") (name "unconnected-(U$5-~{INT}-Pad23)") (class "Default")
      (node (ref "U$5") (pin "23") (pinfunction "~{INT}_23") (pintype "bidirectional"))
    )
  )
)
